# relays.net
KiCad netlist of a schematic drawn in EAGLE
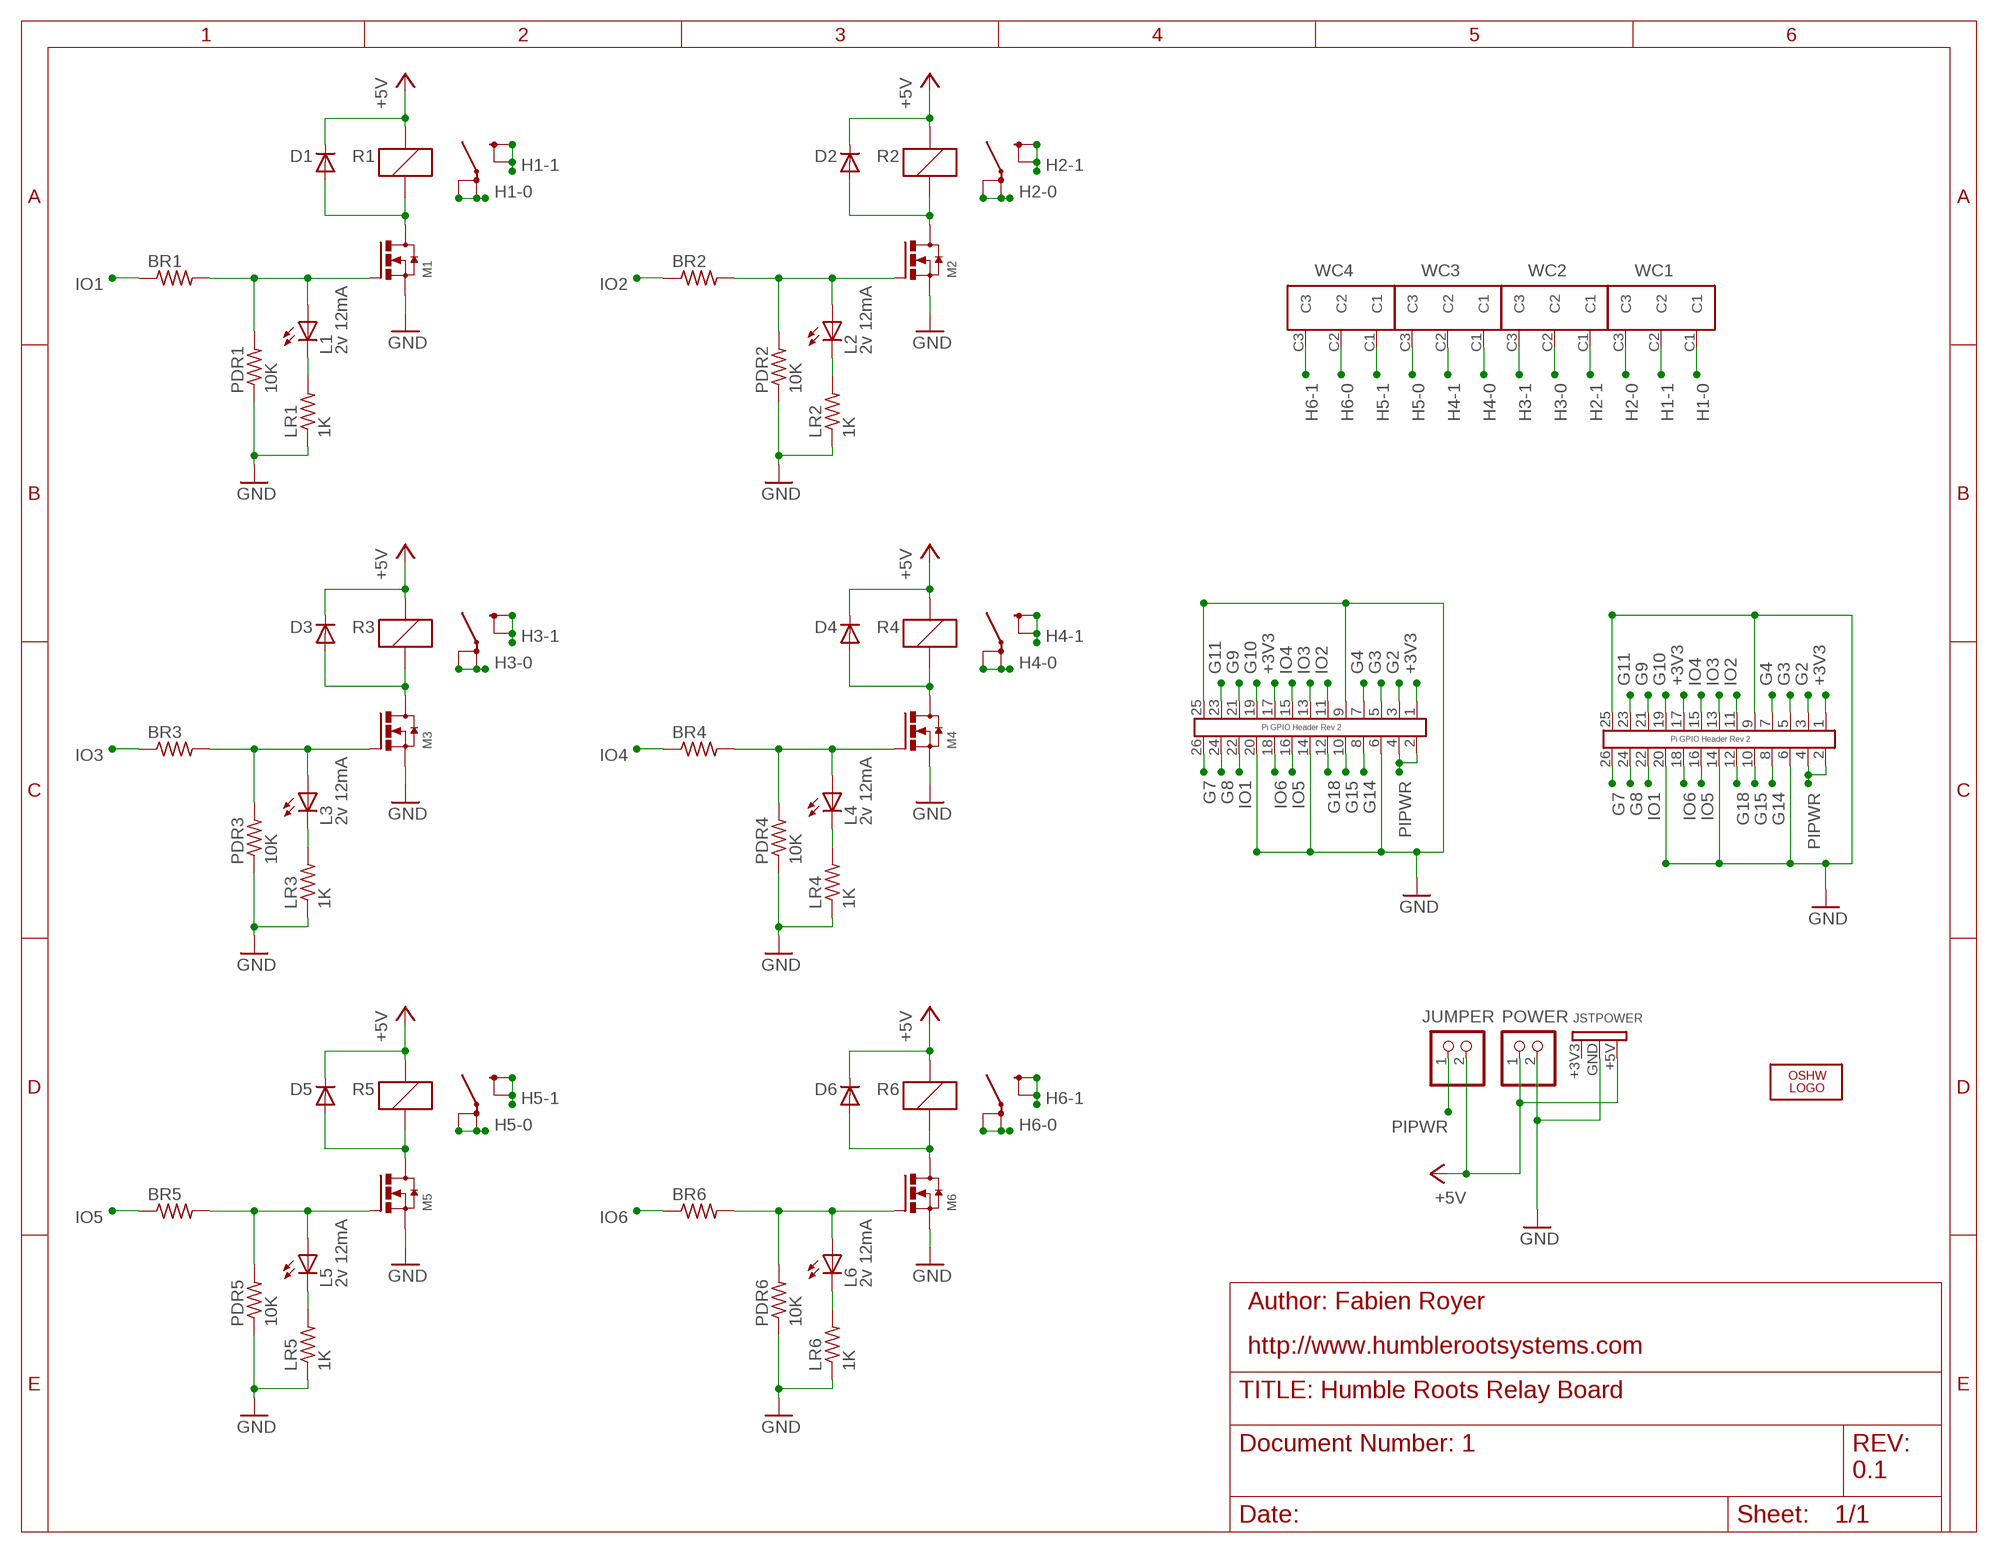
[diagram p0: schematic, sheet 1]

(export (version "E")
  (design (tool "Eeschema 10.0.6"))
  (components
    (comp (ref "BR1")
      (value "R-US_0207/10")
      (footprint "eagle-import:0207_10")
      (libsource (lib "eagle-import") (part "R-US_0207/10"))
    )
    (comp (ref "BR2")
      (value "R-US_0207/10")
      (footprint "eagle-import:0207_10")
      (libsource (lib "eagle-import") (part "R-US_0207/10"))
    )
    (comp (ref "BR3")
      (value "R-US_0207/10")
      (footprint "eagle-import:0207_10")
      (libsource (lib "eagle-import") (part "R-US_0207/10"))
    )
    (comp (ref "BR4")
      (value "R-US_0207/10")
      (footprint "eagle-import:0207_10")
      (libsource (lib "eagle-import") (part "R-US_0207/10"))
    )
    (comp (ref "BR5")
      (value "R-US_0207/10")
      (footprint "eagle-import:0207_10")
      (libsource (lib "eagle-import") (part "R-US_0207/10"))
    )
    (comp (ref "BR6")
      (value "R-US_0207/10")
      (footprint "eagle-import:0207_10")
      (libsource (lib "eagle-import") (part "R-US_0207/10"))
    )
    (comp (ref "D1")
      (value "1N4004")
      (footprint "eagle-import:DO41-10")
      (libsource (lib "eagle-import") (part "1N4004"))
    )
    (comp (ref "D2")
      (value "1N4004")
      (footprint "eagle-import:DO41-10")
      (libsource (lib "eagle-import") (part "1N4004"))
    )
    (comp (ref "D3")
      (value "1N4004")
      (footprint "eagle-import:DO41-10")
      (libsource (lib "eagle-import") (part "1N4004"))
    )
    (comp (ref "D4")
      (value "1N4004")
      (footprint "eagle-import:DO41-10")
      (libsource (lib "eagle-import") (part "1N4004"))
    )
    (comp (ref "D5")
      (value "1N4004")
      (footprint "eagle-import:DO41-10")
      (libsource (lib "eagle-import") (part "1N4004"))
    )
    (comp (ref "D6")
      (value "1N4004")
      (footprint "eagle-import:DO41-10")
      (libsource (lib "eagle-import") (part "1N4004"))
    )
    (comp (ref "JSTPOWER")
      (value "JST_PH_3_POSITIONS_TOP_ENTRY_THROUGH_HOLE")
      (footprint "eagle-import:JST_PH_3_POSITIONS_TOP_ENTRY_THROUGH_HOLE")
      (libsource (lib "eagle-import") (part "JST_PH_3_POSITIONS_TOP_ENTRY_THROUGH_HOLE"))
    )
    (comp (ref "JUMPER")
      (value "5V")
      (footprint "eagle-import:1X02")
      (libsource (lib "eagle-import") (part "PINHD-1X2"))
    )
    (comp (ref "L1")
      (value "2v 12mA")
      (footprint "eagle-import:LED3MM")
      (libsource (lib "eagle-import") (part "LED3MM"))
    )
    (comp (ref "L2")
      (value "2v 12mA")
      (footprint "eagle-import:LED3MM")
      (libsource (lib "eagle-import") (part "LED3MM"))
    )
    (comp (ref "L3")
      (value "2v 12mA")
      (footprint "eagle-import:LED3MM")
      (libsource (lib "eagle-import") (part "LED3MM"))
    )
    (comp (ref "L4")
      (value "2v 12mA")
      (footprint "eagle-import:LED3MM")
      (libsource (lib "eagle-import") (part "LED3MM"))
    )
    (comp (ref "L5")
      (value "2v 12mA")
      (footprint "eagle-import:LED3MM")
      (libsource (lib "eagle-import") (part "LED3MM"))
    )
    (comp (ref "L6")
      (value "2v 12mA")
      (footprint "eagle-import:LED3MM")
      (libsource (lib "eagle-import") (part "LED3MM"))
    )
    (comp (ref "LOGO1")
      (value "OSHW_LOGO_6MILX0200-NT")
      (footprint "eagle-import:OSHW_6X200_NOTEXT")
      (libsource (lib "eagle-import") (part "OSHW_LOGO_6MILX0200-NT"))
    )
    (comp (ref "LR1")
      (value "1K")
      (footprint "eagle-import:0207_10")
      (libsource (lib "eagle-import") (part "R-US_0207/10"))
    )
    (comp (ref "LR2")
      (value "1K")
      (footprint "eagle-import:0207_10")
      (libsource (lib "eagle-import") (part "R-US_0207/10"))
    )
    (comp (ref "LR3")
      (value "1K")
      (footprint "eagle-import:0207_10")
      (libsource (lib "eagle-import") (part "R-US_0207/10"))
    )
    (comp (ref "LR4")
      (value "1K")
      (footprint "eagle-import:0207_10")
      (libsource (lib "eagle-import") (part "R-US_0207/10"))
    )
    (comp (ref "LR5")
      (value "1K")
      (footprint "eagle-import:0207_10")
      (libsource (lib "eagle-import") (part "R-US_0207/10"))
    )
    (comp (ref "LR6")
      (value "1K")
      (footprint "eagle-import:0207_10")
      (libsource (lib "eagle-import") (part "R-US_0207/10"))
    )
    (comp (ref "M1")
      (value "FAIRCHILD_2N700X_N-CHANNEL_MOSFET_TO92")
      (footprint "eagle-import:FAIRCHILD_2N700X_TO92")
      (libsource (lib "eagle-import") (part "FAIRCHILD_2N700X_N-CHANNEL_MOSFET_TO92"))
    )
    (comp (ref "M2")
      (value "FAIRCHILD_2N700X_N-CHANNEL_MOSFET_TO92")
      (footprint "eagle-import:FAIRCHILD_2N700X_TO92")
      (libsource (lib "eagle-import") (part "FAIRCHILD_2N700X_N-CHANNEL_MOSFET_TO92"))
    )
    (comp (ref "M3")
      (value "FAIRCHILD_2N700X_N-CHANNEL_MOSFET_TO92")
      (footprint "eagle-import:FAIRCHILD_2N700X_TO92")
      (libsource (lib "eagle-import") (part "FAIRCHILD_2N700X_N-CHANNEL_MOSFET_TO92"))
    )
    (comp (ref "M4")
      (value "FAIRCHILD_2N700X_N-CHANNEL_MOSFET_TO92")
      (footprint "eagle-import:FAIRCHILD_2N700X_TO92")
      (libsource (lib "eagle-import") (part "FAIRCHILD_2N700X_N-CHANNEL_MOSFET_TO92"))
    )
    (comp (ref "M5")
      (value "FAIRCHILD_2N700X_N-CHANNEL_MOSFET_TO92")
      (footprint "eagle-import:FAIRCHILD_2N700X_TO92")
      (libsource (lib "eagle-import") (part "FAIRCHILD_2N700X_N-CHANNEL_MOSFET_TO92"))
    )
    (comp (ref "M6")
      (value "FAIRCHILD_2N700X_N-CHANNEL_MOSFET_TO92")
      (footprint "eagle-import:FAIRCHILD_2N700X_TO92")
      (libsource (lib "eagle-import") (part "FAIRCHILD_2N700X_N-CHANNEL_MOSFET_TO92"))
    )
    (comp (ref "PDR1")
      (value "10K")
      (footprint "eagle-import:0207_10")
      (libsource (lib "eagle-import") (part "R-US_0207/10"))
    )
    (comp (ref "PDR2")
      (value "10K")
      (footprint "eagle-import:0207_10")
      (libsource (lib "eagle-import") (part "R-US_0207/10"))
    )
    (comp (ref "PDR3")
      (value "10K")
      (footprint "eagle-import:0207_10")
      (libsource (lib "eagle-import") (part "R-US_0207/10"))
    )
    (comp (ref "PDR4")
      (value "10K")
      (footprint "eagle-import:0207_10")
      (libsource (lib "eagle-import") (part "R-US_0207/10"))
    )
    (comp (ref "PDR5")
      (value "10K")
      (footprint "eagle-import:0207_10")
      (libsource (lib "eagle-import") (part "R-US_0207/10"))
    )
    (comp (ref "PDR6")
      (value "10K")
      (footprint "eagle-import:0207_10")
      (libsource (lib "eagle-import") (part "R-US_0207/10"))
    )
    (comp (ref "POWER")
      (value "5V")
      (footprint "eagle-import:1X02")
      (libsource (lib "eagle-import") (part "PINHD-1X2"))
    )
    (comp (ref "R1")
      (value "SCHRACK_POWER_PCB_RELAY_RZ_16A_NO")
      (footprint "eagle-import:SCHRACK_POWER_PCB_RELAY_RZ_16A")
      (libsource (lib "eagle-import") (part "SCHRACK_POWER_PCB_RELAY_RZ_16A_NO"))
    )
    (comp (ref "R2")
      (value "SCHRACK_POWER_PCB_RELAY_RZ_16A_NO")
      (footprint "eagle-import:SCHRACK_POWER_PCB_RELAY_RZ_16A")
      (libsource (lib "eagle-import") (part "SCHRACK_POWER_PCB_RELAY_RZ_16A_NO"))
    )
    (comp (ref "R3")
      (value "SCHRACK_POWER_PCB_RELAY_RZ_16A_NO")
      (footprint "eagle-import:SCHRACK_POWER_PCB_RELAY_RZ_16A")
      (libsource (lib "eagle-import") (part "SCHRACK_POWER_PCB_RELAY_RZ_16A_NO"))
    )
    (comp (ref "R4")
      (value "SCHRACK_POWER_PCB_RELAY_RZ_16A_NO")
      (footprint "eagle-import:SCHRACK_POWER_PCB_RELAY_RZ_16A")
      (libsource (lib "eagle-import") (part "SCHRACK_POWER_PCB_RELAY_RZ_16A_NO"))
    )
    (comp (ref "R5")
      (value "SCHRACK_POWER_PCB_RELAY_RZ_16A_NO")
      (footprint "eagle-import:SCHRACK_POWER_PCB_RELAY_RZ_16A")
      (libsource (lib "eagle-import") (part "SCHRACK_POWER_PCB_RELAY_RZ_16A_NO"))
    )
    (comp (ref "R6")
      (value "SCHRACK_POWER_PCB_RELAY_RZ_16A_NO")
      (footprint "eagle-import:SCHRACK_POWER_PCB_RELAY_RZ_16A")
      (libsource (lib "eagle-import") (part "SCHRACK_POWER_PCB_RELAY_RZ_16A_NO"))
    )
    (comp (ref "U$5")
      (value "PI_GPIO_13X2_PIN_HEADER")
      (footprint "eagle-import:PIN_HEADER_13X2_POSITIONS_DIL")
      (libsource (lib "eagle-import") (part "PI_GPIO_13X2_PIN_HEADER"))
    )
    (comp (ref "U$6")
      (value "PI_GPIO_13X2_PIN_HEADER")
      (footprint "eagle-import:PIN_HEADER_13X2_POSITIONS_DIL")
      (libsource (lib "eagle-import") (part "PI_GPIO_13X2_PIN_HEADER"))
    )
    (comp (ref "WC1")
      (value "PHOENIX_WIRE_CONTACT_3_POSITIONS_GENERIC")
      (footprint "eagle-import:PHOENIX_WIRE_CONTACT_3_POSITIONS_GENERIC")
      (libsource (lib "eagle-import") (part "PHOENIX_WIRE_CONTACT_3_POSITIONS_GENERIC"))
    )
    (comp (ref "WC2")
      (value "PHOENIX_WIRE_CONTACT_3_POSITIONS_GENERIC")
      (footprint "eagle-import:PHOENIX_WIRE_CONTACT_3_POSITIONS_GENERIC")
      (libsource (lib "eagle-import") (part "PHOENIX_WIRE_CONTACT_3_POSITIONS_GENERIC"))
    )
    (comp (ref "WC3")
      (value "PHOENIX_WIRE_CONTACT_3_POSITIONS_GENERIC")
      (footprint "eagle-import:PHOENIX_WIRE_CONTACT_3_POSITIONS_GENERIC")
      (libsource (lib "eagle-import") (part "PHOENIX_WIRE_CONTACT_3_POSITIONS_GENERIC"))
    )
    (comp (ref "WC4")
      (value "PHOENIX_WIRE_CONTACT_3_POSITIONS_GENERIC")
      (footprint "eagle-import:PHOENIX_WIRE_CONTACT_3_POSITIONS_GENERIC")
      (libsource (lib "eagle-import") (part "PHOENIX_WIRE_CONTACT_3_POSITIONS_GENERIC"))
    )
  )
  (nets
    (net (code "1") (name "+5V") (class "Default")
      (node (ref "D1") (pin "C") (pinfunction "C_C") (pintype "passive"))
      (node (ref "D2") (pin "C") (pinfunction "C_C") (pintype "passive"))
      (node (ref "D3") (pin "C") (pinfunction "C_C") (pintype "passive"))
      (node (ref "D4") (pin "C") (pinfunction "C_C") (pintype "passive"))
      (node (ref "D5") (pin "C") (pinfunction "C_C") (pintype "passive"))
      (node (ref "D6") (pin "C") (pinfunction "C_C") (pintype "passive"))
      (node (ref "JSTPOWER") (pin "+5V") (pinfunction "+5V_+5V") (pintype "passive"))
      (node (ref "JUMPER") (pin "2") (pinfunction "2_2") (pintype "passive"))
      (node (ref "POWER") (pin "1") (pinfunction "1_1") (pintype "passive"))
      (node (ref "R1") (pin "COIL_A1") (pinfunction "COIL_A1_COIL_A1") (pintype "passive"))
      (node (ref "R2") (pin "COIL_A1") (pinfunction "COIL_A1_COIL_A1") (pintype "passive"))
      (node (ref "R3") (pin "COIL_A1") (pinfunction "COIL_A1_COIL_A1") (pintype "passive"))
      (node (ref "R4") (pin "COIL_A1") (pinfunction "COIL_A1_COIL_A1") (pintype "passive"))
      (node (ref "R5") (pin "COIL_A1") (pinfunction "COIL_A1_COIL_A1") (pintype "passive"))
      (node (ref "R6") (pin "COIL_A1") (pinfunction "COIL_A1_COIL_A1") (pintype "passive"))
    )
    (net (code "2") (name "/+3V3") (class "Default")
      (node (ref "U$5") (pin "1") (pinfunction "P1_3V3_1") (pintype "power_in"))
      (node (ref "U$5") (pin "17") (pinfunction "P17_3V3_17") (pintype "power_in"))
      (node (ref "U$6") (pin "1") (pinfunction "P1_3V3_1") (pintype "power_in"))
      (node (ref "U$6") (pin "17") (pinfunction "P17_3V3_17") (pintype "power_in"))
    )
    (net (code "3") (name "/G2") (class "Default")
      (node (ref "U$5") (pin "3") (pinfunction "P3_GPIO2_SDA_3") (pintype "bidirectional"))
      (node (ref "U$6") (pin "3") (pinfunction "P3_GPIO2_SDA_3") (pintype "bidirectional"))
    )
    (net (code "4") (name "/G3") (class "Default")
      (node (ref "U$5") (pin "5") (pinfunction "P5_GPIO3_SCL_5") (pintype "bidirectional"))
      (node (ref "U$6") (pin "5") (pinfunction "P5_GPIO3_SCL_5") (pintype "bidirectional"))
    )
    (net (code "5") (name "/G4") (class "Default")
      (node (ref "U$5") (pin "7") (pinfunction "P7_GPIO4_7") (pintype "bidirectional"))
      (node (ref "U$6") (pin "7") (pinfunction "P7_GPIO4_7") (pintype "bidirectional"))
    )
    (net (code "6") (name "/G7") (class "Default")
      (node (ref "U$5") (pin "26") (pinfunction "P26_GPIO7_SPI0_CE1_26") (pintype "bidirectional"))
      (node (ref "U$6") (pin "26") (pinfunction "P26_GPIO7_SPI0_CE1_26") (pintype "bidirectional"))
    )
    (net (code "7") (name "/G8") (class "Default")
      (node (ref "U$5") (pin "24") (pinfunction "P24_GPIO8_SPI0_CE0_24") (pintype "bidirectional"))
      (node (ref "U$6") (pin "24") (pinfunction "P24_GPIO8_SPI0_CE0_24") (pintype "bidirectional"))
    )
    (net (code "8") (name "/G9") (class "Default")
      (node (ref "U$5") (pin "21") (pinfunction "P21_GPIO9_SPI0_MISO_21") (pintype "bidirectional"))
      (node (ref "U$6") (pin "21") (pinfunction "P21_GPIO9_SPI0_MISO_21") (pintype "bidirectional"))
    )
    (net (code "9") (name "/G10") (class "Default")
      (node (ref "U$5") (pin "19") (pinfunction "P19_GPIO10_SPI0_MOSI_19") (pintype "bidirectional"))
      (node (ref "U$6") (pin "19") (pinfunction "P19_GPIO10_SPI0_MOSI_19") (pintype "bidirectional"))
    )
    (net (code "10") (name "/G11") (class "Default")
      (node (ref "U$5") (pin "23") (pinfunction "P23_GPIO11_SPI0_SCLK_23") (pintype "bidirectional"))
      (node (ref "U$6") (pin "23") (pinfunction "P23_GPIO11_SPI0_SCLK_23") (pintype "bidirectional"))
    )
    (net (code "11") (name "/G14") (class "Default")
      (node (ref "U$5") (pin "8") (pinfunction "P8_GPIO14_UART0_TXD_8") (pintype "bidirectional"))
      (node (ref "U$6") (pin "8") (pinfunction "P8_GPIO14_UART0_TXD_8") (pintype "bidirectional"))
    )
    (net (code "12") (name "/G15") (class "Default")
      (node (ref "U$5") (pin "10") (pinfunction "P10_GPIO15_UART0_RXD_10") (pintype "bidirectional"))
      (node (ref "U$6") (pin "10") (pinfunction "P10_GPIO15_UART0_RXD_10") (pintype "bidirectional"))
    )
    (net (code "13") (name "/G18") (class "Default")
      (node (ref "U$5") (pin "12") (pinfunction "P12_GPIO18_12") (pintype "bidirectional"))
      (node (ref "U$6") (pin "12") (pinfunction "P12_GPIO18_12") (pintype "bidirectional"))
    )
    (net (code "14") (name "/H1-0") (class "Default")
      (node (ref "R1") (pin "11A_LOAD") (pinfunction "11A_LOAD_11A_LOAD") (pintype "passive"))
      (node (ref "R1") (pin "11B_LOAD") (pinfunction "11B_LOAD_11B_LOAD") (pintype "passive"))
      (node (ref "WC1") (pin "C1") (pinfunction "C1_C1") (pintype "passive"))
    )
    (net (code "15") (name "/H1-1") (class "Default")
      (node (ref "R1") (pin "14A_LOAD") (pinfunction "14A_LOAD_14A_LOAD") (pintype "passive"))
      (node (ref "R1") (pin "14B_LOAD") (pinfunction "14B_LOAD_14B_LOAD") (pintype "passive"))
      (node (ref "WC1") (pin "C2") (pinfunction "C2_C2") (pintype "passive"))
    )
    (net (code "16") (name "/H2-0") (class "Default")
      (node (ref "R2") (pin "11A_LOAD") (pinfunction "11A_LOAD_11A_LOAD") (pintype "passive"))
      (node (ref "R2") (pin "11B_LOAD") (pinfunction "11B_LOAD_11B_LOAD") (pintype "passive"))
      (node (ref "WC1") (pin "C3") (pinfunction "C3_C3") (pintype "passive"))
    )
    (net (code "17") (name "/H2-1") (class "Default")
      (node (ref "R2") (pin "14A_LOAD") (pinfunction "14A_LOAD_14A_LOAD") (pintype "passive"))
      (node (ref "R2") (pin "14B_LOAD") (pinfunction "14B_LOAD_14B_LOAD") (pintype "passive"))
      (node (ref "WC2") (pin "C1") (pinfunction "C1_C1") (pintype "passive"))
    )
    (net (code "18") (name "/H3-0") (class "Default")
      (node (ref "R3") (pin "11A_LOAD") (pinfunction "11A_LOAD_11A_LOAD") (pintype "passive"))
      (node (ref "R3") (pin "11B_LOAD") (pinfunction "11B_LOAD_11B_LOAD") (pintype "passive"))
      (node (ref "WC2") (pin "C2") (pinfunction "C2_C2") (pintype "passive"))
    )
    (net (code "19") (name "/H3-1") (class "Default")
      (node (ref "R3") (pin "14A_LOAD") (pinfunction "14A_LOAD_14A_LOAD") (pintype "passive"))
      (node (ref "R3") (pin "14B_LOAD") (pinfunction "14B_LOAD_14B_LOAD") (pintype "passive"))
      (node (ref "WC2") (pin "C3") (pinfunction "C3_C3") (pintype "passive"))
    )
    (net (code "20") (name "/H4-0") (class "Default")
      (node (ref "R4") (pin "11A_LOAD") (pinfunction "11A_LOAD_11A_LOAD") (pintype "passive"))
      (node (ref "R4") (pin "11B_LOAD") (pinfunction "11B_LOAD_11B_LOAD") (pintype "passive"))
      (node (ref "WC3") (pin "C1") (pinfunction "C1_C1") (pintype "passive"))
    )
    (net (code "21") (name "/H4-1") (class "Default")
      (node (ref "R4") (pin "14A_LOAD") (pinfunction "14A_LOAD_14A_LOAD") (pintype "passive"))
      (node (ref "R4") (pin "14B_LOAD") (pinfunction "14B_LOAD_14B_LOAD") (pintype "passive"))
      (node (ref "WC3") (pin "C2") (pinfunction "C2_C2") (pintype "passive"))
    )
    (net (code "22") (name "/H5-0") (class "Default")
      (node (ref "R5") (pin "11A_LOAD") (pinfunction "11A_LOAD_11A_LOAD") (pintype "passive"))
      (node (ref "R5") (pin "11B_LOAD") (pinfunction "11B_LOAD_11B_LOAD") (pintype "passive"))
      (node (ref "WC3") (pin "C3") (pinfunction "C3_C3") (pintype "passive"))
    )
    (net (code "23") (name "/H5-1") (class "Default")
      (node (ref "R5") (pin "14A_LOAD") (pinfunction "14A_LOAD_14A_LOAD") (pintype "passive"))
      (node (ref "R5") (pin "14B_LOAD") (pinfunction "14B_LOAD_14B_LOAD") (pintype "passive"))
      (node (ref "WC4") (pin "C1") (pinfunction "C1_C1") (pintype "passive"))
    )
    (net (code "24") (name "/H6-0") (class "Default")
      (node (ref "R6") (pin "11A_LOAD") (pinfunction "11A_LOAD_11A_LOAD") (pintype "passive"))
      (node (ref "R6") (pin "11B_LOAD") (pinfunction "11B_LOAD_11B_LOAD") (pintype "passive"))
      (node (ref "WC4") (pin "C2") (pinfunction "C2_C2") (pintype "passive"))
    )
    (net (code "25") (name "/H6-1") (class "Default")
      (node (ref "R6") (pin "14A_LOAD") (pinfunction "14A_LOAD_14A_LOAD") (pintype "passive"))
      (node (ref "R6") (pin "14B_LOAD") (pinfunction "14B_LOAD_14B_LOAD") (pintype "passive"))
      (node (ref "WC4") (pin "C3") (pinfunction "C3_C3") (pintype "passive"))
    )
    (net (code "26") (name "/IO1") (class "Default")
      (node (ref "BR1") (pin "1") (pinfunction "1_1") (pintype "passive"))
      (node (ref "U$5") (pin "22") (pinfunction "P22_GPIO25_22") (pintype "bidirectional"))
      (node (ref "U$6") (pin "22") (pinfunction "P22_GPIO25_22") (pintype "bidirectional"))
    )
    (net (code "27") (name "/IO2") (class "Default")
      (node (ref "BR2") (pin "1") (pinfunction "1_1") (pintype "passive"))
      (node (ref "U$5") (pin "11") (pinfunction "P11_GPIO17_11") (pintype "bidirectional"))
      (node (ref "U$6") (pin "11") (pinfunction "P11_GPIO17_11") (pintype "bidirectional"))
    )
    (net (code "28") (name "/IO3") (class "Default")
      (node (ref "BR3") (pin "1") (pinfunction "1_1") (pintype "passive"))
      (node (ref "U$5") (pin "13") (pinfunction "P13_GPIO27_13") (pintype "bidirectional"))
      (node (ref "U$6") (pin "13") (pinfunction "P13_GPIO27_13") (pintype "bidirectional"))
    )
    (net (code "29") (name "/IO4") (class "Default")
      (node (ref "BR4") (pin "1") (pinfunction "1_1") (pintype "passive"))
      (node (ref "U$5") (pin "15") (pinfunction "P15_GPIO22_15") (pintype "bidirectional"))
      (node (ref "U$6") (pin "15") (pinfunction "P15_GPIO22_15") (pintype "bidirectional"))
    )
    (net (code "30") (name "/IO5") (class "Default")
      (node (ref "BR5") (pin "1") (pinfunction "1_1") (pintype "passive"))
      (node (ref "U$5") (pin "16") (pinfunction "P16_GPIO23_16") (pintype "bidirectional"))
      (node (ref "U$6") (pin "16") (pinfunction "P16_GPIO23_16") (pintype "bidirectional"))
    )
    (net (code "31") (name "/IO6") (class "Default")
      (node (ref "BR6") (pin "1") (pinfunction "1_1") (pintype "passive"))
      (node (ref "U$5") (pin "18") (pinfunction "P18_GPIO24_18") (pintype "bidirectional"))
      (node (ref "U$6") (pin "18") (pinfunction "P18_GPIO24_18") (pintype "bidirectional"))
    )
    (net (code "32") (name "/PIPWR") (class "Default")
      (node (ref "JUMPER") (pin "1") (pinfunction "1_1") (pintype "passive"))
      (node (ref "U$5") (pin "2") (pinfunction "P2_5V_2") (pintype "power_in"))
      (node (ref "U$5") (pin "4") (pinfunction "P4_5V_4") (pintype "power_in"))
      (node (ref "U$6") (pin "2") (pinfunction "P2_5V_2") (pintype "power_in"))
      (node (ref "U$6") (pin "4") (pinfunction "P4_5V_4") (pintype "power_in"))
    )
    (net (code "33") (name "GND") (class "Default")
      (node (ref "JSTPOWER") (pin "GND") (pinfunction "GND_GND") (pintype "passive"))
      (node (ref "LR1") (pin "1") (pinfunction "1_1") (pintype "passive"))
      (node (ref "LR2") (pin "1") (pinfunction "1_1") (pintype "passive"))
      (node (ref "LR3") (pin "1") (pinfunction "1_1") (pintype "passive"))
      (node (ref "LR4") (pin "1") (pinfunction "1_1") (pintype "passive"))
      (node (ref "LR5") (pin "1") (pinfunction "1_1") (pintype "passive"))
      (node (ref "LR6") (pin "1") (pinfunction "1_1") (pintype "passive"))
      (node (ref "M1") (pin "S") (pinfunction "SOURCE_S") (pintype "passive"))
      (node (ref "M2") (pin "S") (pinfunction "SOURCE_S") (pintype "passive"))
      (node (ref "M3") (pin "S") (pinfunction "SOURCE_S") (pintype "passive"))
      (node (ref "M4") (pin "S") (pinfunction "SOURCE_S") (pintype "passive"))
      (node (ref "M5") (pin "S") (pinfunction "SOURCE_S") (pintype "passive"))
      (node (ref "M6") (pin "S") (pinfunction "SOURCE_S") (pintype "passive"))
      (node (ref "PDR1") (pin "1") (pinfunction "1_1") (pintype "passive"))
      (node (ref "PDR2") (pin "1") (pinfunction "1_1") (pintype "passive"))
      (node (ref "PDR3") (pin "1") (pinfunction "1_1") (pintype "passive"))
      (node (ref "PDR4") (pin "1") (pinfunction "1_1") (pintype "passive"))
      (node (ref "PDR5") (pin "1") (pinfunction "1_1") (pintype "passive"))
      (node (ref "PDR6") (pin "1") (pinfunction "1_1") (pintype "passive"))
      (node (ref "POWER") (pin "2") (pinfunction "2_2") (pintype "passive"))
      (node (ref "U$5") (pin "14") (pinfunction "P14_GND_14") (pintype "passive"))
      (node (ref "U$5") (pin "20") (pinfunction "P20_GND_20") (pintype "passive"))
      (node (ref "U$5") (pin "25") (pinfunction "P25_GND_25") (pintype "passive"))
      (node (ref "U$5") (pin "6") (pinfunction "P6_GND_6") (pintype "passive"))
      (node (ref "U$5") (pin "9") (pinfunction "P9_GND_9") (pintype "passive"))
      (node (ref "U$6") (pin "14") (pinfunction "P14_GND_14") (pintype "passive"))
      (node (ref "U$6") (pin "20") (pinfunction "P20_GND_20") (pintype "passive"))
      (node (ref "U$6") (pin "25") (pinfunction "P25_GND_25") (pintype "passive"))
      (node (ref "U$6") (pin "6") (pinfunction "P6_GND_6") (pintype "passive"))
      (node (ref "U$6") (pin "9") (pinfunction "P9_GND_9") (pintype "passive"))
    )
    (net (code "34") (name "Net-(L1-C)") (class "Default")
      (node (ref "L1") (pin "K") (pinfunction "C_K") (pintype "passive"))
      (node (ref "LR1") (pin "2") (pinfunction "2_2") (pintype "passive"))
    )
    (net (code "35") (name "Net-(L2-C)") (class "Default")
      (node (ref "L2") (pin "K") (pinfunction "C_K") (pintype "passive"))
      (node (ref "LR2") (pin "2") (pinfunction "2_2") (pintype "passive"))
    )
    (net (code "36") (name "Net-(L3-C)") (class "Default")
      (node (ref "L3") (pin "K") (pinfunction "C_K") (pintype "passive"))
      (node (ref "LR3") (pin "2") (pinfunction "2_2") (pintype "passive"))
    )
    (net (code "37") (name "Net-(L4-C)") (class "Default")
      (node (ref "L4") (pin "K") (pinfunction "C_K") (pintype "passive"))
      (node (ref "LR4") (pin "2") (pinfunction "2_2") (pintype "passive"))
    )
    (net (code "38") (name "Net-(L5-C)") (class "Default")
      (node (ref "L5") (pin "K") (pinfunction "C_K") (pintype "passive"))
      (node (ref "LR5") (pin "2") (pinfunction "2_2") (pintype "passive"))
    )
    (net (code "39") (name "Net-(L6-C)") (class "Default")
      (node (ref "L6") (pin "K") (pinfunction "C_K") (pintype "passive"))
      (node (ref "LR6") (pin "2") (pinfunction "2_2") (pintype "passive"))
    )
    (net (code "40") (name "Net-(M1-DRAIN)") (class "Default")
      (node (ref "D1") (pin "A") (pinfunction "A_A") (pintype "passive"))
      (node (ref "M1") (pin "D") (pinfunction "DRAIN_D") (pintype "passive"))
      (node (ref "R1") (pin "COIL_A2") (pinfunction "COIL_A2_COIL_A2") (pintype "passive"))
    )
    (net (code "41") (name "Net-(M1-GATE)") (class "Default")
      (node (ref "BR1") (pin "2") (pinfunction "2_2") (pintype "passive"))
      (node (ref "L1") (pin "A") (pinfunction "A_A") (pintype "passive"))
      (node (ref "M1") (pin "G") (pinfunction "GATE_G") (pintype "passive"))
      (node (ref "PDR1") (pin "2") (pinfunction "2_2") (pintype "passive"))
    )
    (net (code "42") (name "Net-(M2-DRAIN)") (class "Default")
      (node (ref "D2") (pin "A") (pinfunction "A_A") (pintype "passive"))
      (node (ref "M2") (pin "D") (pinfunction "DRAIN_D") (pintype "passive"))
      (node (ref "R2") (pin "COIL_A2") (pinfunction "COIL_A2_COIL_A2") (pintype "passive"))
    )
    (net (code "43") (name "Net-(M2-GATE)") (class "Default")
      (node (ref "BR2") (pin "2") (pinfunction "2_2") (pintype "passive"))
      (node (ref "L2") (pin "A") (pinfunction "A_A") (pintype "passive"))
      (node (ref "M2") (pin "G") (pinfunction "GATE_G") (pintype "passive"))
      (node (ref "PDR2") (pin "2") (pinfunction "2_2") (pintype "passive"))
    )
    (net (code "44") (name "Net-(M3-DRAIN)") (class "Default")
      (node (ref "D3") (pin "A") (pinfunction "A_A") (pintype "passive"))
      (node (ref "M3") (pin "D") (pinfunction "DRAIN_D") (pintype "passive"))
      (node (ref "R3") (pin "COIL_A2") (pinfunction "COIL_A2_COIL_A2") (pintype "passive"))
    )
    (net (code "45") (name "Net-(M3-GATE)") (class "Default")
      (node (ref "BR3") (pin "2") (pinfunction "2_2") (pintype "passive"))
      (node (ref "L3") (pin "A") (pinfunction "A_A") (pintype "passive"))
      (node (ref "M3") (pin "G") (pinfunction "GATE_G") (pintype "passive"))
      (node (ref "PDR3") (pin "2") (pinfunction "2_2") (pintype "passive"))
    )
    (net (code "46") (name "Net-(M4-DRAIN)") (class "Default")
      (node (ref "D4") (pin "A") (pinfunction "A_A") (pintype "passive"))
      (node (ref "M4") (pin "D") (pinfunction "DRAIN_D") (pintype "passive"))
      (node (ref "R4") (pin "COIL_A2") (pinfunction "COIL_A2_COIL_A2") (pintype "passive"))
    )
    (net (code "47") (name "Net-(M4-GATE)") (class "Default")
      (node (ref "BR4") (pin "2") (pinfunction "2_2") (pintype "passive"))
      (node (ref "L4") (pin "A") (pinfunction "A_A") (pintype "passive"))
      (node (ref "M4") (pin "G") (pinfunction "GATE_G") (pintype "passive"))
      (node (ref "PDR4") (pin "2") (pinfunction "2_2") (pintype "passive"))
    )
    (net (code "48") (name "Net-(M5-DRAIN)") (class "Default")
      (node (ref "D5") (pin "A") (pinfunction "A_A") (pintype "passive"))
      (node (ref "M5") (pin "D") (pinfunction "DRAIN_D") (pintype "passive"))
      (node (ref "R5") (pin "COIL_A2") (pinfunction "COIL_A2_COIL_A2") (pintype "passive"))
    )
    (net (code "49") (name "Net-(M5-GATE)") (class "Default")
      (node (ref "BR5") (pin "2") (pinfunction "2_2") (pintype "passive"))
      (node (ref "L5") (pin "A") (pinfunction "A_A") (pintype "passive"))
      (node (ref "M5") (pin "G") (pinfunction "GATE_G") (pintype "passive"))
      (node (ref "PDR5") (pin "2") (pinfunction "2_2") (pintype "passive"))
    )
    (net (code "50") (name "Net-(M6-DRAIN)") (class "Default")
      (node (ref "D6") (pin "A") (pinfunction "A_A") (pintype "passive"))
      (node (ref "M6") (pin "D") (pinfunction "DRAIN_D") (pintype "passive"))
      (node (ref "R6") (pin "COIL_A2") (pinfunction "COIL_A2_COIL_A2") (pintype "passive"))
    )
    (net (code "51") (name "Net-(M6-GATE)") (class "Default")
      (node (ref "BR6") (pin "2") (pinfunction "2_2") (pintype "passive"))
      (node (ref "L6") (pin "A") (pinfunction "A_A") (pintype "passive"))
      (node (ref "M6") (pin "G") (pinfunction "GATE_G") (pintype "passive"))
      (node (ref "PDR6") (pin "2") (pinfunction "2_2") (pintype "passive"))
    )
    (net (code "52") (name "unconnected-(JSTPOWER-Pad+3V3)") (class "Default")
      (node (ref "JSTPOWER") (pin "+3V3") (pinfunction "+3V3_+3V3") (pintype "passive"))
    )
  )
)
